# ESP_LoRa_Scale_V1_61.net
KiCad netlist of a schematic drawn in EAGLE
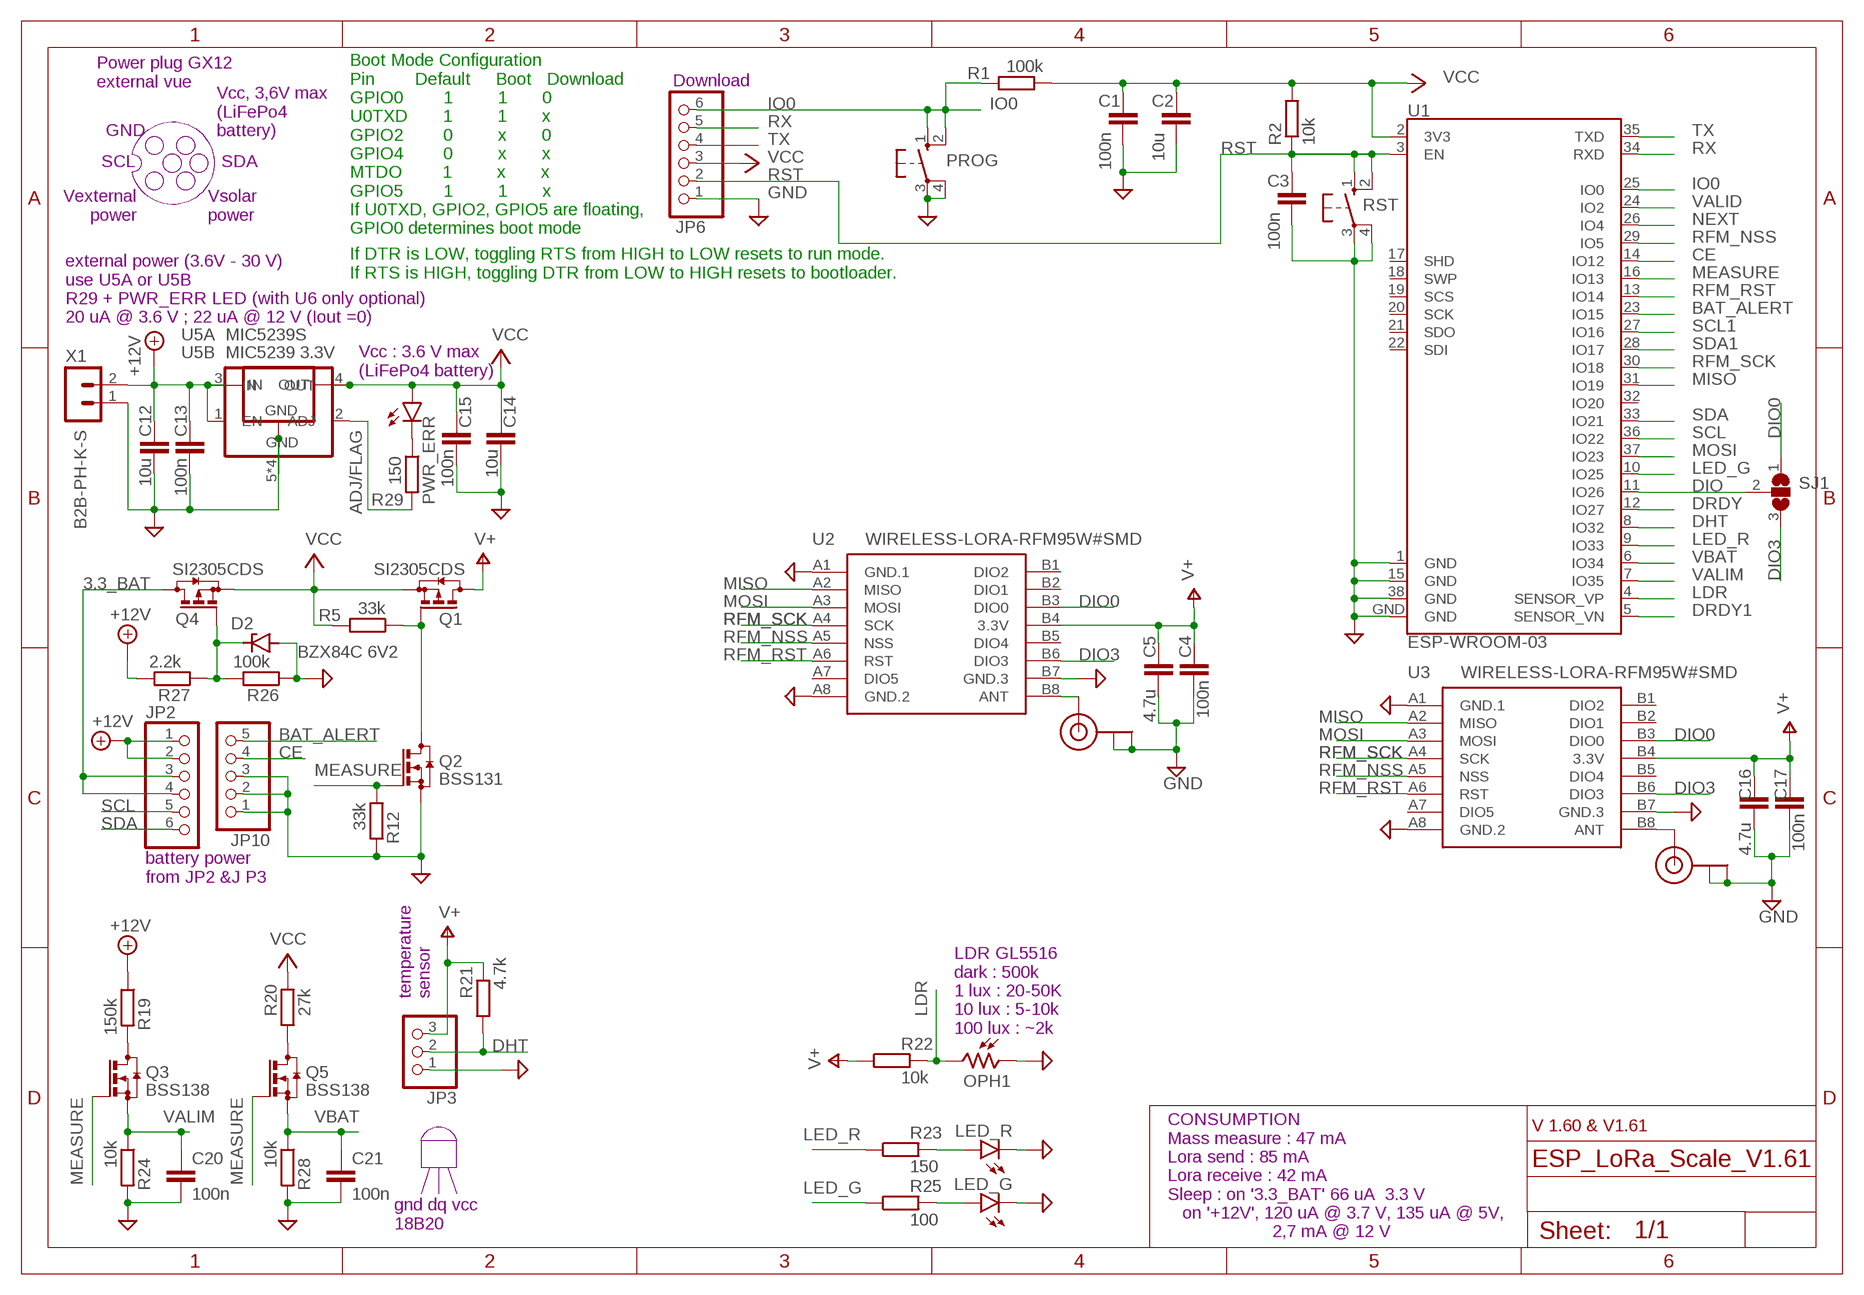
[diagram p0: schematic, sheet 1]

(export (version "E")
  (design (tool "Eeschema 10.0.6"))
  (components
    (comp (ref "C1")
      (value "100n")
      (footprint "eagle-import:C1206")
      (libsource (lib "eagle-import") (part "CC1206"))
    )
    (comp (ref "C2")
      (value "10u")
      (footprint "eagle-import:C1210")
      (libsource (lib "eagle-import") (part "CC1210"))
    )
    (comp (ref "C3")
      (value "100n")
      (footprint "eagle-import:C1206")
      (libsource (lib "eagle-import") (part "CC1206"))
    )
    (comp (ref "C4")
      (value "100n")
      (footprint "eagle-import:C1206")
      (libsource (lib "eagle-import") (part "CC1206"))
    )
    (comp (ref "C5")
      (value "4.7u")
      (footprint "eagle-import:C1210")
      (libsource (lib "eagle-import") (part "CC1210"))
    )
    (comp (ref "C12")
      (value "10u")
      (footprint "eagle-import:C1210")
      (libsource (lib "eagle-import") (part "CC1210"))
    )
    (comp (ref "C13")
      (value "100n")
      (footprint "eagle-import:C1206")
      (libsource (lib "eagle-import") (part "CC1206"))
    )
    (comp (ref "C14")
      (value "10u")
      (footprint "eagle-import:C1210")
      (libsource (lib "eagle-import") (part "CC1210"))
    )
    (comp (ref "C15")
      (value "100n")
      (footprint "eagle-import:C1206")
      (libsource (lib "eagle-import") (part "CC1206"))
    )
    (comp (ref "C16")
      (value "4.7u")
      (footprint "eagle-import:C1210")
      (libsource (lib "eagle-import") (part "CC1210"))
    )
    (comp (ref "C17")
      (value "100n")
      (footprint "eagle-import:C1206")
      (libsource (lib "eagle-import") (part "CC1206"))
    )
    (comp (ref "C20")
      (value "100n")
      (footprint "eagle-import:C1206")
      (libsource (lib "eagle-import") (part "CC1206"))
    )
    (comp (ref "C21")
      (value "100n")
      (footprint "eagle-import:C1206")
      (libsource (lib "eagle-import") (part "CC1206"))
    )
    (comp (ref "D2")
      (value "BZX84C 6V2")
      (footprint "eagle-import:TO236")
      (libsource (lib "eagle-import") (part "BZX84CSMD"))
    )
    (comp (ref "J1")
      (value "U.FL")
      (footprint "eagle-import:U.FL")
      (libsource (lib "eagle-import") (part "U.FL"))
    )
    (comp (ref "J2")
      (value "U.FL")
      (footprint "eagle-import:U.FL")
      (libsource (lib "eagle-import") (part "U.FL"))
    )
    (comp (ref "JP2")
      (value "PINHD-1X6")
      (footprint "eagle-import:1X06")
      (libsource (lib "eagle-import") (part "PINHD-1X6"))
    )
    (comp (ref "JP3")
      (value "PINHD-1X3")
      (footprint "eagle-import:1X03")
      (libsource (lib "eagle-import") (part "PINHD-1X3"))
    )
    (comp (ref "JP6")
      (value "PINHD-1X6")
      (footprint "eagle-import:1X06")
      (libsource (lib "eagle-import") (part "PINHD-1X6"))
    )
    (comp (ref "JP10")
      (value "PINHD-1X5")
      (footprint "eagle-import:1X05")
      (libsource (lib "eagle-import") (part "PINHD-1X5"))
    )
    (comp (ref "LED_G")
      (value "LEDSMT1206")
      (footprint "eagle-import:1206")
      (libsource (lib "eagle-import") (part "LEDSMT1206"))
    )
    (comp (ref "LED_R")
      (value "LEDSMT1206")
      (footprint "eagle-import:1206")
      (libsource (lib "eagle-import") (part "LEDSMT1206"))
    )
    (comp (ref "OPH1")
      (value "VT93N2")
      (footprint "eagle-import:VT900")
      (libsource (lib "eagle-import") (part "VT93N2"))
    )
    (comp (ref "PROG")
      (value "10-XX")
      (footprint "eagle-import:B3F-10XX")
      (fields (field (name "MPN") "B3F-1000"))
      (libsource (lib "eagle-import") (part "10-XX"))
    )
    (comp (ref "PWR_ERR")
      (value "LEDSMT1206")
      (footprint "eagle-import:1206")
      (libsource (lib "eagle-import") (part "LEDSMT1206"))
    )
    (comp (ref "Q1")
      (value "SI2305CDS")
      (footprint "eagle-import:SOT23")
      (libsource (lib "eagle-import") (part "SI2305CDS"))
    )
    (comp (ref "Q2")
      (value "BSS131")
      (footprint "eagle-import:SOT23")
      (libsource (lib "eagle-import") (part "BSS131"))
    )
    (comp (ref "Q3")
      (value "BSS138")
      (footprint "eagle-import:SOT23")
      (libsource (lib "eagle-import") (part "BSS138"))
    )
    (comp (ref "Q4")
      (value "SI2305CDS")
      (footprint "eagle-import:SOT23")
      (libsource (lib "eagle-import") (part "SI2305CDS"))
    )
    (comp (ref "Q5")
      (value "BSS138")
      (footprint "eagle-import:SOT23")
      (libsource (lib "eagle-import") (part "BSS138"))
    )
    (comp (ref "R1")
      (value "100k")
      (footprint "eagle-import:R1206")
      (libsource (lib "eagle-import") (part "RR1206"))
    )
    (comp (ref "R2")
      (value "10k")
      (footprint "eagle-import:R1206")
      (libsource (lib "eagle-import") (part "RR1206"))
    )
    (comp (ref "R5")
      (value "33k")
      (footprint "eagle-import:R1206")
      (libsource (lib "eagle-import") (part "RR1206"))
    )
    (comp (ref "R12")
      (value "33k")
      (footprint "eagle-import:R1206")
      (libsource (lib "eagle-import") (part "RR1206"))
    )
    (comp (ref "R19")
      (value "150k")
      (footprint "eagle-import:R1206")
      (libsource (lib "eagle-import") (part "RR1206"))
    )
    (comp (ref "R20")
      (value "27k")
      (footprint "eagle-import:R1206")
      (libsource (lib "eagle-import") (part "RR1206"))
    )
    (comp (ref "R21")
      (value "4.7k")
      (footprint "eagle-import:R1206")
      (libsource (lib "eagle-import") (part "RR1206"))
    )
    (comp (ref "R22")
      (value "10k")
      (footprint "eagle-import:R1206")
      (libsource (lib "eagle-import") (part "RR1206"))
    )
    (comp (ref "R23")
      (value "150")
      (footprint "eagle-import:R1206")
      (libsource (lib "eagle-import") (part "RR1206"))
    )
    (comp (ref "R24")
      (value "10k")
      (footprint "eagle-import:R1206")
      (libsource (lib "eagle-import") (part "RR1206"))
    )
    (comp (ref "R25")
      (value "100")
      (footprint "eagle-import:R1206")
      (libsource (lib "eagle-import") (part "RR1206"))
    )
    (comp (ref "R26")
      (value "100k")
      (footprint "eagle-import:R1206")
      (libsource (lib "eagle-import") (part "RR1206"))
    )
    (comp (ref "R27")
      (value "2.2k")
      (footprint "eagle-import:R1206")
      (libsource (lib "eagle-import") (part "RR1206"))
    )
    (comp (ref "R28")
      (value "10k")
      (footprint "eagle-import:R1206")
      (libsource (lib "eagle-import") (part "RR1206"))
    )
    (comp (ref "R29")
      (value "150")
      (footprint "eagle-import:R1206")
      (libsource (lib "eagle-import") (part "RR1206"))
    )
    (comp (ref "RST")
      (value "10-XX")
      (footprint "eagle-import:B3F-10XX")
      (fields (field (name "MPN") "B3F-1000"))
      (libsource (lib "eagle-import") (part "10-XX"))
    )
    (comp (ref "SJ1")
      (value "SJ2W")
      (footprint "eagle-import:SJ_2")
      (libsource (lib "eagle-import") (part "SJ2W"))
    )
    (comp (ref "U1")
      (value "ESP-WROOM-03")
      (footprint "eagle-import:ESP-WROOM-03")
      (libsource (lib "eagle-import") (part "ESP-WROOM-03"))
    )
    (comp (ref "U2")
      (value "WIRELESS-LORA-RFM95W#SMD")
      (footprint "eagle-import:WIRELESS-LORA-RFM95W#SMD")
      (libsource (lib "eagle-import") (part "WIRELESS-LORA-RFM95W#SMD"))
    )
    (comp (ref "U3")
      (value "WIRELESS-LORA-RFM95W#SMD")
      (footprint "eagle-import:WIRELESS-LORA-RFM95W#SMD")
      (libsource (lib "eagle-import") (part "WIRELESS-LORA-RFM95W#SMD"))
    )
    (comp (ref "U5A")
      (value "MIC5239 3.3V")
      (footprint "eagle-import:MSOP08")
      (libsource (lib "eagle-import") (part "MIC5239-ADJMM"))
    )
    (comp (ref "U5B")
      (value "MIC5239S")
      (footprint "eagle-import:SOT223")
      (libsource (lib "eagle-import") (part "MIC5239S"))
    )
    (comp (ref "X1")
      (value "B2B-PH-K-S")
      (footprint "eagle-import:B2B-PH-K-S")
      (libsource (lib "eagle-import") (part "B2B-PH-K-S"))
    )
  )
  (nets
    (net (code "1") (name "+12V") (class "Default")
      (node (ref "C12") (pin "1") (pinfunction "1_1") (pintype "passive"))
      (node (ref "C13") (pin "1") (pinfunction "1_1") (pintype "passive"))
      (node (ref "JP2") (pin "1") (pinfunction "1_1") (pintype "passive"))
      (node (ref "JP2") (pin "2") (pinfunction "2_2") (pintype "passive"))
      (node (ref "R19") (pin "1") (pinfunction "1_1") (pintype "passive"))
      (node (ref "R27") (pin "2") (pinfunction "2_2") (pintype "passive"))
      (node (ref "U5A") (pin "1") (pinfunction "EN_1") (pintype "input"))
      (node (ref "U5A") (pin "3") (pinfunction "IN_3") (pintype "input"))
      (node (ref "U5B") (pin "1") (pinfunction "IN_1") (pintype "input"))
      (node (ref "X1") (pin "2") (pinfunction "2_2") (pintype "passive"))
    )
    (net (code "2") (name "/3.3_BAT") (class "Default")
      (node (ref "JP2") (pin "3") (pinfunction "3_3") (pintype "passive"))
      (node (ref "JP2") (pin "4") (pinfunction "4_4") (pintype "passive"))
      (node (ref "Q4") (pin "3") (pinfunction "D_3") (pintype "passive"))
    )
    (net (code "3") (name "/ADJ{slash}FLAG") (class "Default")
      (node (ref "R29") (pin "2") (pinfunction "2_2") (pintype "passive"))
      (node (ref "U5A") (pin "2") (pinfunction "ADJ_2") (pintype "passive"))
    )
    (net (code "4") (name "/BAT_ALERT") (class "Default")
      (node (ref "JP10") (pin "5") (pinfunction "5_5") (pintype "passive"))
      (node (ref "U1") (pin "23") (pinfunction "IO15_23") (pintype "bidirectional"))
    )
    (net (code "5") (name "/CE") (class "Default")
      (node (ref "JP10") (pin "4") (pinfunction "4_4") (pintype "passive"))
      (node (ref "U1") (pin "14") (pinfunction "IO12_14") (pintype "bidirectional"))
    )
    (net (code "6") (name "/DHT") (class "Default")
      (node (ref "JP3") (pin "2") (pinfunction "2_2") (pintype "passive"))
      (node (ref "R21") (pin "1") (pinfunction "1_1") (pintype "passive"))
      (node (ref "U1") (pin "8") (pinfunction "IO32_8") (pintype "bidirectional"))
    )
    (net (code "7") (name "/DIO") (class "Default")
      (node (ref "SJ1") (pin "2") (pinfunction "2_2") (pintype "passive"))
      (node (ref "U1") (pin "11") (pinfunction "IO26_11") (pintype "bidirectional"))
    )
    (net (code "8") (name "/DIO0") (class "Default")
      (node (ref "SJ1") (pin "1") (pinfunction "1_1") (pintype "passive"))
      (node (ref "U2") (pin "B3") (pinfunction "DIO0_B3") (pintype "bidirectional"))
      (node (ref "U3") (pin "B3") (pinfunction "DIO0_B3") (pintype "bidirectional"))
    )
    (net (code "9") (name "/DIO3") (class "Default")
      (node (ref "SJ1") (pin "3") (pinfunction "3_3") (pintype "passive"))
      (node (ref "U2") (pin "B6") (pinfunction "DIO3_B6") (pintype "bidirectional"))
      (node (ref "U3") (pin "B6") (pinfunction "DIO3_B6") (pintype "bidirectional"))
    )
    (net (code "10") (name "/DRDY") (class "Default")
      (node (ref "U1") (pin "12") (pinfunction "IO27_12") (pintype "bidirectional"))
    )
    (net (code "11") (name "/DRDY1") (class "Default")
      (node (ref "U1") (pin "5") (pinfunction "SENSOR_VN_5") (pintype "bidirectional"))
    )
    (net (code "12") (name "/IO0") (class "Default")
      (node (ref "JP6") (pin "6") (pinfunction "6_6") (pintype "passive"))
      (node (ref "PROG") (pin "1") (pinfunction "S_1") (pintype "passive"))
      (node (ref "PROG") (pin "2") (pinfunction "S1_2") (pintype "passive"))
      (node (ref "R1") (pin "2") (pinfunction "2_2") (pintype "passive"))
      (node (ref "U1") (pin "25") (pinfunction "IO0_25") (pintype "bidirectional"))
    )
    (net (code "13") (name "/LDR") (class "Default")
      (node (ref "OPH1") (pin "2") (pinfunction "2_2") (pintype "passive"))
      (node (ref "R22") (pin "2") (pinfunction "2_2") (pintype "passive"))
      (node (ref "U1") (pin "4") (pinfunction "SENSOR_VP_4") (pintype "bidirectional"))
    )
    (net (code "14") (name "/LED_G") (class "Default")
      (node (ref "R25") (pin "1") (pinfunction "1_1") (pintype "passive"))
      (node (ref "U1") (pin "10") (pinfunction "IO25_10") (pintype "bidirectional"))
    )
    (net (code "15") (name "/LED_R") (class "Default")
      (node (ref "R23") (pin "1") (pinfunction "1_1") (pintype "passive"))
      (node (ref "U1") (pin "9") (pinfunction "IO33_9") (pintype "bidirectional"))
    )
    (net (code "16") (name "/MEASURE") (class "Default")
      (node (ref "Q2") (pin "1") (pinfunction "G_1") (pintype "passive"))
      (node (ref "Q3") (pin "1") (pinfunction "G_1") (pintype "passive"))
      (node (ref "Q5") (pin "1") (pinfunction "G_1") (pintype "passive"))
      (node (ref "R12") (pin "1") (pinfunction "1_1") (pintype "passive"))
      (node (ref "U1") (pin "16") (pinfunction "IO13_16") (pintype "bidirectional"))
    )
    (net (code "17") (name "/MISO") (class "Default")
      (node (ref "U1") (pin "31") (pinfunction "IO19_31") (pintype "bidirectional"))
      (node (ref "U2") (pin "A2") (pinfunction "MISO_A2") (pintype "bidirectional"))
      (node (ref "U3") (pin "A2") (pinfunction "MISO_A2") (pintype "bidirectional"))
    )
    (net (code "18") (name "/MOSI") (class "Default")
      (node (ref "U1") (pin "37") (pinfunction "IO23_37") (pintype "bidirectional"))
      (node (ref "U2") (pin "A3") (pinfunction "MOSI_A3") (pintype "bidirectional"))
      (node (ref "U3") (pin "A3") (pinfunction "MOSI_A3") (pintype "bidirectional"))
    )
    (net (code "19") (name "/NEXT") (class "Default")
      (node (ref "U1") (pin "26") (pinfunction "IO4_26") (pintype "bidirectional"))
    )
    (net (code "20") (name "/RFM_NSS") (class "Default")
      (node (ref "U1") (pin "29") (pinfunction "IO5_29") (pintype "bidirectional"))
      (node (ref "U2") (pin "A5") (pinfunction "NSS_A5") (pintype "bidirectional"))
      (node (ref "U3") (pin "A5") (pinfunction "NSS_A5") (pintype "bidirectional"))
    )
    (net (code "21") (name "/RFM_RST") (class "Default")
      (node (ref "U1") (pin "13") (pinfunction "IO14_13") (pintype "bidirectional"))
      (node (ref "U2") (pin "A6") (pinfunction "RST_A6") (pintype "bidirectional"))
      (node (ref "U3") (pin "A6") (pinfunction "RST_A6") (pintype "bidirectional"))
    )
    (net (code "22") (name "/RFM_SCK") (class "Default")
      (node (ref "U1") (pin "30") (pinfunction "IO18_30") (pintype "bidirectional"))
      (node (ref "U2") (pin "A4") (pinfunction "SCK_A4") (pintype "bidirectional"))
      (node (ref "U3") (pin "A4") (pinfunction "SCK_A4") (pintype "bidirectional"))
    )
    (net (code "23") (name "/RST") (class "Default")
      (node (ref "C3") (pin "1") (pinfunction "1_1") (pintype "passive"))
      (node (ref "JP6") (pin "2") (pinfunction "2_2") (pintype "passive"))
      (node (ref "R2") (pin "1") (pinfunction "1_1") (pintype "passive"))
      (node (ref "RST") (pin "1") (pinfunction "S_1") (pintype "passive"))
      (node (ref "RST") (pin "2") (pinfunction "S1_2") (pintype "passive"))
      (node (ref "U1") (pin "3") (pinfunction "EN_3") (pintype "bidirectional"))
    )
    (net (code "24") (name "/RX") (class "Default")
      (node (ref "JP6") (pin "5") (pinfunction "5_5") (pintype "passive"))
      (node (ref "U1") (pin "34") (pinfunction "RXD_34") (pintype "bidirectional"))
    )
    (net (code "25") (name "/SCL") (class "Default")
      (node (ref "JP2") (pin "5") (pinfunction "5_5") (pintype "passive"))
      (node (ref "U1") (pin "36") (pinfunction "IO22_36") (pintype "bidirectional"))
    )
    (net (code "26") (name "/SCL1") (class "Default")
      (node (ref "U1") (pin "27") (pinfunction "IO16_27") (pintype "bidirectional"))
    )
    (net (code "27") (name "/SDA") (class "Default")
      (node (ref "JP2") (pin "6") (pinfunction "6_6") (pintype "passive"))
      (node (ref "U1") (pin "33") (pinfunction "IO21_33") (pintype "bidirectional"))
    )
    (net (code "28") (name "/SDA1") (class "Default")
      (node (ref "U1") (pin "28") (pinfunction "IO17_28") (pintype "bidirectional"))
    )
    (net (code "29") (name "/TX") (class "Default")
      (node (ref "JP6") (pin "4") (pinfunction "4_4") (pintype "passive"))
      (node (ref "U1") (pin "35") (pinfunction "TXD_35") (pintype "bidirectional"))
    )
    (net (code "30") (name "/VALID") (class "Default")
      (node (ref "U1") (pin "24") (pinfunction "IO2_24") (pintype "bidirectional"))
    )
    (net (code "31") (name "/VALIM") (class "Default")
      (node (ref "C20") (pin "1") (pinfunction "1_1") (pintype "passive"))
      (node (ref "Q3") (pin "2") (pinfunction "S_2") (pintype "passive"))
      (node (ref "R24") (pin "1") (pinfunction "1_1") (pintype "passive"))
      (node (ref "U1") (pin "7") (pinfunction "IO35_7") (pintype "bidirectional"))
    )
    (net (code "32") (name "/VBAT") (class "Default")
      (node (ref "C21") (pin "1") (pinfunction "1_1") (pintype "passive"))
      (node (ref "Q5") (pin "2") (pinfunction "S_2") (pintype "passive"))
      (node (ref "R28") (pin "1") (pinfunction "1_1") (pintype "passive"))
      (node (ref "U1") (pin "6") (pinfunction "IO34_6") (pintype "bidirectional"))
    )
    (net (code "33") (name "GND") (class "Default")
      (node (ref "C1") (pin "2") (pinfunction "2_2") (pintype "passive"))
      (node (ref "C12") (pin "2") (pinfunction "2_2") (pintype "passive"))
      (node (ref "C13") (pin "2") (pinfunction "2_2") (pintype "passive"))
      (node (ref "C14") (pin "2") (pinfunction "2_2") (pintype "passive"))
      (node (ref "C15") (pin "2") (pinfunction "2_2") (pintype "passive"))
      (node (ref "C16") (pin "2") (pinfunction "2_2") (pintype "passive"))
      (node (ref "C17") (pin "2") (pinfunction "2_2") (pintype "passive"))
      (node (ref "C2") (pin "2") (pinfunction "2_2") (pintype "passive"))
      (node (ref "C20") (pin "2") (pinfunction "2_2") (pintype "passive"))
      (node (ref "C21") (pin "2") (pinfunction "2_2") (pintype "passive"))
      (node (ref "C3") (pin "2") (pinfunction "2_2") (pintype "passive"))
      (node (ref "C4") (pin "2") (pinfunction "2_2") (pintype "passive"))
      (node (ref "C5") (pin "2") (pinfunction "2_2") (pintype "passive"))
      (node (ref "D2") (pin "A") (pinfunction "A_A") (pintype "passive"))
      (node (ref "J1") (pin "1") (pinfunction "GND_1") (pintype "passive"))
      (node (ref "J1") (pin "2") (pinfunction "GND_2") (pintype "passive"))
      (node (ref "J2") (pin "1") (pinfunction "GND_1") (pintype "passive"))
      (node (ref "J2") (pin "2") (pinfunction "GND_2") (pintype "passive"))
      (node (ref "JP10") (pin "1") (pinfunction "1_1") (pintype "passive"))
      (node (ref "JP10") (pin "2") (pinfunction "2_2") (pintype "passive"))
      (node (ref "JP10") (pin "3") (pinfunction "3_3") (pintype "passive"))
      (node (ref "JP3") (pin "1") (pinfunction "1_1") (pintype "passive"))
      (node (ref "JP6") (pin "1") (pinfunction "1_1") (pintype "passive"))
      (node (ref "LED_G") (pin "C") (pinfunction "C_C") (pintype "passive"))
      (node (ref "LED_R") (pin "C") (pinfunction "C_C") (pintype "passive"))
      (node (ref "OPH1") (pin "1") (pinfunction "1_1") (pintype "passive"))
      (node (ref "PROG") (pin "3") (pinfunction "P_3") (pintype "passive"))
      (node (ref "PROG") (pin "4") (pinfunction "P1_4") (pintype "passive"))
      (node (ref "Q2") (pin "2") (pinfunction "S_2") (pintype "passive"))
      (node (ref "R12") (pin "2") (pinfunction "2_2") (pintype "passive"))
      (node (ref "R24") (pin "2") (pinfunction "2_2") (pintype "passive"))
      (node (ref "R26") (pin "1") (pinfunction "1_1") (pintype "passive"))
      (node (ref "R28") (pin "2") (pinfunction "2_2") (pintype "passive"))
      (node (ref "RST") (pin "3") (pinfunction "P_3") (pintype "passive"))
      (node (ref "RST") (pin "4") (pinfunction "P1_4") (pintype "passive"))
      (node (ref "U1") (pin "1") (pinfunction "GND_1") (pintype "bidirectional"))
      (node (ref "U1") (pin "15") (pinfunction "GND_15") (pintype "bidirectional"))
      (node (ref "U1") (pin "38") (pinfunction "GND_38") (pintype "bidirectional"))
      (node (ref "U1") (pin "GND") (pinfunction "GND_GND") (pintype "bidirectional"))
      (node (ref "U2") (pin "A1") (pinfunction "GND.1_A1") (pintype "power_in"))
      (node (ref "U2") (pin "A8") (pinfunction "GND.2_A8") (pintype "power_in"))
      (node (ref "U2") (pin "B7") (pinfunction "GND.3_B7") (pintype "power_in"))
      (node (ref "U3") (pin "A1") (pinfunction "GND.1_A1") (pintype "power_in"))
      (node (ref "U3") (pin "A8") (pinfunction "GND.2_A8") (pintype "power_in"))
      (node (ref "U3") (pin "B7") (pinfunction "GND.3_B7") (pintype "power_in"))
      (node (ref "U5A") (pin "5") (pinfunction "GND_5") (pintype "power_in"))
      (node (ref "U5A") (pin "6") (pinfunction "GND_6") (pintype "power_in"))
      (node (ref "U5A") (pin "7") (pinfunction "GND_7") (pintype "power_in"))
      (node (ref "U5A") (pin "8") (pinfunction "GND_8") (pintype "power_in"))
      (node (ref "U5B") (pin "2") (pinfunction "GND_2") (pintype "passive"))
      (node (ref "U5B") (pin "4") (pinfunction "GND_4") (pintype "passive"))
      (node (ref "X1") (pin "1") (pinfunction "1_1") (pintype "passive"))
    )
    (net (code "34") (name "Net-(J1-SIGNAL)") (class "Default")
      (node (ref "J1") (pin "3") (pinfunction "SIGNAL_3") (pintype "passive"))
      (node (ref "U3") (pin "B8") (pinfunction "ANT_B8") (pintype "passive"))
    )
    (net (code "35") (name "Net-(J2-SIGNAL)") (class "Default")
      (node (ref "J2") (pin "3") (pinfunction "SIGNAL_3") (pintype "passive"))
      (node (ref "U2") (pin "B8") (pinfunction "ANT_B8") (pintype "passive"))
    )
    (net (code "36") (name "Net-(LED_G-PadA)") (class "Default")
      (node (ref "LED_G") (pin "A") (pinfunction "A_A") (pintype "passive"))
      (node (ref "R25") (pin "2") (pinfunction "2_2") (pintype "passive"))
    )
    (net (code "37") (name "Net-(LED_R-PadA)") (class "Default")
      (node (ref "LED_R") (pin "A") (pinfunction "A_A") (pintype "passive"))
      (node (ref "R23") (pin "2") (pinfunction "2_2") (pintype "passive"))
    )
    (net (code "38") (name "Net-(PWR_ERR-PadC)") (class "Default")
      (node (ref "PWR_ERR") (pin "C") (pinfunction "C_C") (pintype "passive"))
      (node (ref "R29") (pin "1") (pinfunction "1_1") (pintype "passive"))
    )
    (net (code "39") (name "Net-(Q1-G)") (class "Default")
      (node (ref "Q1") (pin "1") (pinfunction "G_1") (pintype "passive"))
      (node (ref "Q2") (pin "3") (pinfunction "D_3") (pintype "passive"))
      (node (ref "R5") (pin "1") (pinfunction "1_1") (pintype "passive"))
    )
    (net (code "40") (name "Net-(Q3-D)") (class "Default")
      (node (ref "Q3") (pin "3") (pinfunction "D_3") (pintype "passive"))
      (node (ref "R19") (pin "2") (pinfunction "2_2") (pintype "passive"))
    )
    (net (code "41") (name "Net-(Q4-G)") (class "Default")
      (node (ref "D2") (pin "C") (pinfunction "C_C") (pintype "passive"))
      (node (ref "Q4") (pin "1") (pinfunction "G_1") (pintype "passive"))
      (node (ref "R26") (pin "2") (pinfunction "2_2") (pintype "passive"))
      (node (ref "R27") (pin "1") (pinfunction "1_1") (pintype "passive"))
    )
    (net (code "42") (name "Net-(Q5-D)") (class "Default")
      (node (ref "Q5") (pin "3") (pinfunction "D_3") (pintype "passive"))
      (node (ref "R20") (pin "1") (pinfunction "1_1") (pintype "passive"))
    )
    (net (code "43") (name "V+") (class "Default")
      (node (ref "C16") (pin "1") (pinfunction "1_1") (pintype "passive"))
      (node (ref "C17") (pin "1") (pinfunction "1_1") (pintype "passive"))
      (node (ref "C4") (pin "1") (pinfunction "1_1") (pintype "passive"))
      (node (ref "C5") (pin "1") (pinfunction "1_1") (pintype "passive"))
      (node (ref "JP3") (pin "3") (pinfunction "3_3") (pintype "passive"))
      (node (ref "Q1") (pin "3") (pinfunction "D_3") (pintype "passive"))
      (node (ref "R21") (pin "2") (pinfunction "2_2") (pintype "passive"))
      (node (ref "R22") (pin "1") (pinfunction "1_1") (pintype "passive"))
      (node (ref "U2") (pin "B4") (pinfunction "3.3V_B4") (pintype "power_in"))
      (node (ref "U3") (pin "B4") (pinfunction "3.3V_B4") (pintype "power_in"))
    )
    (net (code "44") (name "VCC") (class "Default")
      (node (ref "C1") (pin "1") (pinfunction "1_1") (pintype "passive"))
      (node (ref "C14") (pin "1") (pinfunction "1_1") (pintype "passive"))
      (node (ref "C15") (pin "1") (pinfunction "1_1") (pintype "passive"))
      (node (ref "C2") (pin "1") (pinfunction "1_1") (pintype "passive"))
      (node (ref "JP6") (pin "3") (pinfunction "3_3") (pintype "passive"))
      (node (ref "PWR_ERR") (pin "A") (pinfunction "A_A") (pintype "passive"))
      (node (ref "Q1") (pin "2") (pinfunction "S_2") (pintype "passive"))
      (node (ref "Q4") (pin "2") (pinfunction "S_2") (pintype "passive"))
      (node (ref "R1") (pin "1") (pinfunction "1_1") (pintype "passive"))
      (node (ref "R2") (pin "2") (pinfunction "2_2") (pintype "passive"))
      (node (ref "R20") (pin "2") (pinfunction "2_2") (pintype "passive"))
      (node (ref "R5") (pin "2") (pinfunction "2_2") (pintype "passive"))
      (node (ref "U1") (pin "2") (pinfunction "3V3_2") (pintype "bidirectional"))
      (node (ref "U5A") (pin "4") (pinfunction "OUT_4") (pintype "passive"))
      (node (ref "U5B") (pin "3") (pinfunction "OUT_3") (pintype "passive"))
    )
    (net (code "45") (name "unconnected-(U1-IO20-Pad32)") (class "Default")
      (node (ref "U1") (pin "32") (pinfunction "IO20_32") (pintype "bidirectional"))
    )
    (net (code "46") (name "unconnected-(U1-SCK-Pad20)") (class "Default")
      (node (ref "U1") (pin "20") (pinfunction "SCK_20") (pintype "bidirectional"))
    )
    (net (code "47") (name "unconnected-(U1-SCS-Pad19)") (class "Default")
      (node (ref "U1") (pin "19") (pinfunction "SCS_19") (pintype "bidirectional"))
    )
    (net (code "48") (name "unconnected-(U1-SDI-Pad22)") (class "Default")
      (node (ref "U1") (pin "22") (pinfunction "SDI_22") (pintype "bidirectional"))
    )
    (net (code "49") (name "unconnected-(U1-SDO-Pad21)") (class "Default")
      (node (ref "U1") (pin "21") (pinfunction "SDO_21") (pintype "bidirectional"))
    )
    (net (code "50") (name "unconnected-(U1-SHD-Pad17)") (class "Default")
      (node (ref "U1") (pin "17") (pinfunction "SHD_17") (pintype "bidirectional"))
    )
    (net (code "51") (name "unconnected-(U1-SWP-Pad18)") (class "Default")
      (node (ref "U1") (pin "18") (pinfunction "SWP_18") (pintype "bidirectional"))
    )
    (net (code "52") (name "unconnected-(U2-DIO1-PadB2)") (class "Default")
      (node (ref "U2") (pin "B2") (pinfunction "DIO1_B2") (pintype "bidirectional"))
    )
    (net (code "53") (name "unconnected-(U2-DIO2-PadB1)") (class "Default")
      (node (ref "U2") (pin "B1") (pinfunction "DIO2_B1") (pintype "bidirectional"))
    )
    (net (code "54") (name "unconnected-(U2-DIO4-PadB5)") (class "Default")
      (node (ref "U2") (pin "B5") (pinfunction "DIO4_B5") (pintype "bidirectional"))
    )
    (net (code "55") (name "unconnected-(U2-DIO5-PadA7)") (class "Default")
      (node (ref "U2") (pin "A7") (pinfunction "DIO5_A7") (pintype "bidirectional"))
    )
    (net (code "56") (name "unconnected-(U3-DIO1-PadB2)") (class "Default")
      (node (ref "U3") (pin "B2") (pinfunction "DIO1_B2") (pintype "bidirectional"))
    )
    (net (code "57") (name "unconnected-(U3-DIO2-PadB1)") (class "Default")
      (node (ref "U3") (pin "B1") (pinfunction "DIO2_B1") (pintype "bidirectional"))
    )
    (net (code "58") (name "unconnected-(U3-DIO4-PadB5)") (class "Default")
      (node (ref "U3") (pin "B5") (pinfunction "DIO4_B5") (pintype "bidirectional"))
    )
    (net (code "59") (name "unconnected-(U3-DIO5-PadA7)") (class "Default")
      (node (ref "U3") (pin "A7") (pinfunction "DIO5_A7") (pintype "bidirectional"))
    )
  )
)
